# KC_Input_VAS_Schematic_v0_2.net
KiCad netlist of a schematic drawn in Altium Designer
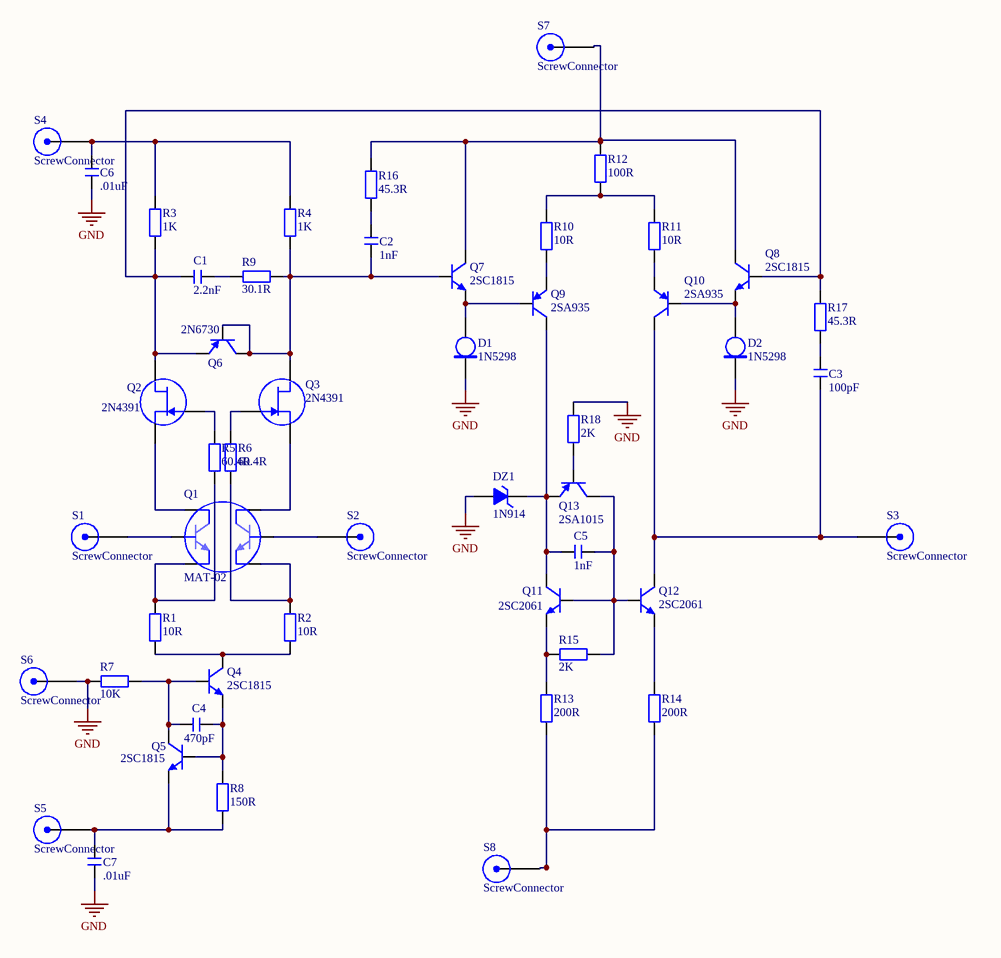
[diagram p0: KC_Input_VAS_Schematic_v0.2.SchDoc]

(export (version "E")
  (design (tool "Eeschema 10.0.6"))
  (components
    (comp (ref "C1")
      (value "2.2nF")
      (footprint "CBB 6.3*6.3*5")
      (description "CBB电容")
      (fields (field (name "版权归属") "源创客"))
      (libsource (lib "电阻-电容-电感") (part "C-CBB"))
    )
    (comp (ref "C2")
      (value "1nF")
      (footprint "CBB 6.3*6.3*5")
      (description "CBB电容")
      (fields (field (name "版权归属") "源创客"))
      (libsource (lib "电阻-电容-电感") (part "C-CBB"))
    )
    (comp (ref "C3")
      (value "100pF")
      (footprint "CBB 6.3*6.3*5")
      (description "CBB电容")
      (fields (field (name "版权归属") "源创客"))
      (libsource (lib "电阻-电容-电感") (part "C-CBB"))
    )
    (comp (ref "C4")
      (value "470pF")
      (footprint "CBB 6.3*6.3*5")
      (description "CBB电容")
      (fields (field (name "版权归属") "源创客"))
      (libsource (lib "电阻-电容-电感") (part "C-CBB"))
    )
    (comp (ref "C5")
      (value "1nF")
      (footprint "CBB 6.3*6.3*5")
      (description "CBB电容")
      (fields (field (name "版权归属") "源创客"))
      (libsource (lib "电阻-电容-电感") (part "C-CBB"))
    )
    (comp (ref "C6")
      (value ".01uF")
      (footprint "CBB 6.3*6.3*5")
      (description "CBB电容")
      (fields (field (name "版权归属") "源创客"))
      (libsource (lib "电阻-电容-电感") (part "C-CBB"))
    )
    (comp (ref "C7")
      (value ".01uF")
      (footprint "CBB 6.3*6.3*5")
      (description "CBB电容")
      (fields (field (name "版权归属") "源创客"))
      (libsource (lib "电阻-电容-电感") (part "C-CBB"))
    )
    (comp (ref "D1")
      (value "1N5298")
      (footprint "DO-41V")
      (description "Current Regulator Diodes")
      (libsource (lib "二极管-整流桥") (part "1N5xxx"))
    )
    (comp (ref "D2")
      (value "1N5298")
      (footprint "DO-41V")
      (description "Current Regulator Diodes")
      (libsource (lib "二极管-整流桥") (part "1N5xxx"))
    )
    (comp (ref "DZ1")
      (value "1N914")
      (footprint "DO-41")
      (description "3V/0.5W稳压管")
      (fields (field (name "版权归属") "源创客"))
      (libsource (lib "二极管-整流桥") (part "1N4619"))
    )
    (comp (ref "Q1")
      (value "MAT-02")
      (footprint "DIP-8")
      (description "孪生对管-NPN型 40V/20ma")
      (libsource (lib "三极管") (part "MAT-02"))
    )
    (comp (ref "Q2")
      (value "2N4391")
      (footprint "TO-18_SMALLHOLE")
      (description "N沟道JFET开关管 40V/150ma")
      (libsource (lib "场效应管") (part "2N4391"))
    )
    (comp (ref "Q3")
      (value "2N4391")
      (footprint "TO-18_SMALLHOLE")
      (description "N沟道JFET开关管 40V/150ma")
      (libsource (lib "场效应管") (part "2N4391"))
    )
    (comp (ref "Q4")
      (value "2SC1815")
      (footprint "TO92A_SmallHole")
      (description "音频放大-NPN型")
      (libsource (lib "三极管") (part "2SC1815"))
    )
    (comp (ref "Q5")
      (value "2SC1815")
      (footprint "TO92A_SmallHole")
      (description "音频放大-NPN型")
      (libsource (lib "三极管") (part "2SC1815"))
    )
    (comp (ref "Q6")
      (value "2N6730")
      (footprint "TO92A_SmallHole")
      (description "中功率放大-PNP型")
      (libsource (lib "三极管") (part "2N6728/6729/6730"))
    )
    (comp (ref "Q7")
      (value "2SC1815")
      (footprint "TO92A_SmallHole")
      (description "音频放大-NPN型")
      (libsource (lib "三极管") (part "2SC1815"))
    )
    (comp (ref "Q8")
      (value "2SC1815")
      (footprint "TO92A_SmallHole")
      (description "音频放大-NPN型")
      (libsource (lib "三极管") (part "2SC1815"))
    )
    (comp (ref "Q9")
      (value "2SA935")
      (footprint "TO92A_SmallHole")
      (description "音频功放-PNP型 50V/500ma")
      (libsource (lib "三极管") (part "2SA935"))
    )
    (comp (ref "Q10")
      (value "2SA935")
      (footprint "TO92A_SmallHole")
      (description "音频功放-PNP型 50V/500ma")
      (libsource (lib "三极管") (part "2SA935"))
    )
    (comp (ref "Q11")
      (value "2SC2061")
      (footprint "TO92A_SmallHole")
      (description "音频放大-NPN型 50V/500ma")
      (libsource (lib "三极管") (part "2SC2061"))
    )
    (comp (ref "Q12")
      (value "2SC2061")
      (footprint "TO92A_SmallHole")
      (description "音频放大-NPN型 50V/500ma")
      (libsource (lib "三极管") (part "2SC2061"))
    )
    (comp (ref "Q13")
      (value "2SA1015")
      (footprint "TO92A_SmallHole")
      (description "音频放大-PNP型")
      (libsource (lib "三极管") (part "2SA1015"))
    )
    (comp (ref "R1")
      (value "10R")
      (footprint "RS 1/4W")
      (description "直插色环电阻")
      (fields (field (name "版权归属") "源创客"))
      (libsource (lib "电阻-电容-电感") (part "R-CRR"))
    )
    (comp (ref "R2")
      (value "10R")
      (footprint "RS 1/4W")
      (description "直插色环电阻")
      (fields (field (name "版权归属") "源创客"))
      (libsource (lib "电阻-电容-电感") (part "R-CRR"))
    )
    (comp (ref "R3")
      (value "1K")
      (footprint "RS 1/4W")
      (description "直插色环电阻")
      (fields (field (name "版权归属") "源创客"))
      (libsource (lib "电阻-电容-电感") (part "R-CRR"))
    )
    (comp (ref "R4")
      (value "1K")
      (footprint "RS 1/4W")
      (description "直插色环电阻")
      (fields (field (name "版权归属") "源创客"))
      (libsource (lib "电阻-电容-电感") (part "R-CRR"))
    )
    (comp (ref "R5")
      (value "60.4R")
      (footprint "RS 1/4W")
      (description "直插色环电阻")
      (fields (field (name "版权归属") "源创客"))
      (libsource (lib "电阻-电容-电感") (part "R-CRR"))
    )
    (comp (ref "R6")
      (value "60.4R")
      (footprint "RS 1/4W")
      (description "直插色环电阻")
      (fields (field (name "版权归属") "源创客"))
      (libsource (lib "电阻-电容-电感") (part "R-CRR"))
    )
    (comp (ref "R7")
      (value "10K")
      (footprint "RS 1/4W")
      (description "直插色环电阻")
      (fields (field (name "版权归属") "源创客"))
      (libsource (lib "电阻-电容-电感") (part "R-CRR"))
    )
    (comp (ref "R8")
      (value "150R")
      (footprint "RS 1/4W")
      (description "直插色环电阻")
      (fields (field (name "版权归属") "源创客"))
      (libsource (lib "电阻-电容-电感") (part "R-CRR"))
    )
    (comp (ref "R9")
      (value "30.1R")
      (footprint "RS 1/4W")
      (description "直插色环电阻")
      (fields (field (name "版权归属") "源创客"))
      (libsource (lib "电阻-电容-电感") (part "R-CRR"))
    )
    (comp (ref "R10")
      (value "10R")
      (footprint "RS 1/4W")
      (description "直插色环电阻")
      (fields (field (name "版权归属") "源创客"))
      (libsource (lib "电阻-电容-电感") (part "R-CRR"))
    )
    (comp (ref "R11")
      (value "10R")
      (footprint "RS 1/4W")
      (description "直插色环电阻")
      (fields (field (name "版权归属") "源创客"))
      (libsource (lib "电阻-电容-电感") (part "R-CRR"))
    )
    (comp (ref "R12")
      (value "100R")
      (footprint "RS 1/4W")
      (description "直插色环电阻")
      (fields (field (name "版权归属") "源创客"))
      (libsource (lib "电阻-电容-电感") (part "R-CRR"))
    )
    (comp (ref "R13")
      (value "200R")
      (footprint "RS 1/4W")
      (description "直插色环电阻")
      (fields (field (name "版权归属") "源创客"))
      (libsource (lib "电阻-电容-电感") (part "R-CRR"))
    )
    (comp (ref "R14")
      (value "200R")
      (footprint "RS 1/4W")
      (description "直插色环电阻")
      (fields (field (name "版权归属") "源创客"))
      (libsource (lib "电阻-电容-电感") (part "R-CRR"))
    )
    (comp (ref "R15")
      (value "2K")
      (footprint "RS 1/4W")
      (description "直插色环电阻")
      (fields (field (name "版权归属") "源创客"))
      (libsource (lib "电阻-电容-电感") (part "R-CRR"))
    )
    (comp (ref "R16")
      (value "45.3R")
      (footprint "RS 1/4W")
      (description "直插色环电阻")
      (fields (field (name "版权归属") "源创客"))
      (libsource (lib "电阻-电容-电感") (part "R-CRR"))
    )
    (comp (ref "R17")
      (value "45.3R")
      (footprint "RS 1/4W")
      (description "直插色环电阻")
      (fields (field (name "版权归属") "源创客"))
      (libsource (lib "电阻-电容-电感") (part "R-CRR"))
    )
    (comp (ref "R18")
      (value "2K")
      (footprint "RS 1/4W")
      (description "直插色环电阻")
      (fields (field (name "版权归属") "源创客"))
      (libsource (lib "电阻-电容-电感") (part "R-CRR"))
    )
    (comp (ref "S1")
      (value "ScrewConnector")
      (footprint "Screw-M3")
      (description "Screw Connector")
      (libsource (lib "Connectors") (part "ScrewConnector"))
    )
    (comp (ref "S2")
      (value "ScrewConnector")
      (footprint "Screw-M3")
      (description "Screw Connector")
      (libsource (lib "Connectors") (part "ScrewConnector"))
    )
    (comp (ref "S3")
      (value "ScrewConnector")
      (footprint "Screw-M3")
      (description "Screw Connector")
      (libsource (lib "Connectors") (part "ScrewConnector"))
    )
    (comp (ref "S4")
      (value "ScrewConnector")
      (footprint "Screw-M3")
      (description "Screw Connector")
      (libsource (lib "Connectors") (part "ScrewConnector"))
    )
    (comp (ref "S5")
      (value "ScrewConnector")
      (footprint "Screw-M3")
      (description "Screw Connector")
      (libsource (lib "Connectors") (part "ScrewConnector"))
    )
    (comp (ref "S6")
      (value "ScrewConnector")
      (footprint "Screw-M3")
      (description "Screw Connector")
      (libsource (lib "Connectors") (part "ScrewConnector"))
    )
    (comp (ref "S7")
      (value "ScrewConnector")
      (footprint "Screw-M3")
      (description "Screw Connector")
      (libsource (lib "Connectors") (part "ScrewConnector"))
    )
    (comp (ref "S8")
      (value "ScrewConnector")
      (footprint "Screw-M3")
      (description "Screw Connector")
      (libsource (lib "Connectors") (part "ScrewConnector"))
    )
  )
  (nets
    (net (code "1") (name "GND") (class "Default")
      (node (ref "C6") (pin "2") (pinfunction "2_2") (pintype "passive"))
      (node (ref "C7") (pin "1") (pinfunction "1_1") (pintype "passive"))
      (node (ref "D1") (pin "1") (pinfunction "Cathode_1") (pintype "passive"))
      (node (ref "D2") (pin "1") (pinfunction "Cathode_1") (pintype "passive"))
      (node (ref "DZ1") (pin "1") (pinfunction "A_1") (pintype "passive"))
      (node (ref "R18") (pin "2") (pinfunction "2_2") (pintype "passive"))
      (node (ref "R7") (pin "1") (pinfunction "1_1") (pintype "passive"))
      (node (ref "S6") (pin "1") (pinfunction "X_1") (pintype "passive"))
    )
    (net (code "2") (name "Net-(C1-Pad2)") (class "Default")
      (node (ref "C1") (pin "2") (pinfunction "2_2") (pintype "passive"))
      (node (ref "R9") (pin "1") (pinfunction "1_1") (pintype "passive"))
    )
    (net (code "3") (name "Net-(C2-Pad1)") (class "Default")
      (node (ref "C2") (pin "1") (pinfunction "1_1") (pintype "passive"))
      (node (ref "R16") (pin "1") (pinfunction "1_1") (pintype "passive"))
    )
    (net (code "4") (name "Net-(C3-Pad2)") (class "Default")
      (node (ref "C3") (pin "2") (pinfunction "2_2") (pintype "passive"))
      (node (ref "R17") (pin "1") (pinfunction "1_1") (pintype "passive"))
    )
    (net (code "5") (name "Net-(D1-Anode)") (class "Default")
      (node (ref "D1") (pin "2") (pinfunction "Anode_2") (pintype "passive"))
      (node (ref "Q7") (pin "1") (pinfunction "E_1") (pintype "passive"))
      (node (ref "Q9") (pin "3") (pinfunction "B_3") (pintype "passive"))
    )
    (net (code "6") (name "Net-(D2-Anode)") (class "Default")
      (node (ref "D2") (pin "2") (pinfunction "Anode_2") (pintype "passive"))
      (node (ref "Q10") (pin "3") (pinfunction "B_3") (pintype "passive"))
      (node (ref "Q8") (pin "1") (pinfunction "E_1") (pintype "passive"))
    )
    (net (code "7") (name "Net-(DZ1-K)") (class "Default")
      (node (ref "C5") (pin "1") (pinfunction "1_1") (pintype "passive"))
      (node (ref "DZ1") (pin "2") (pinfunction "K_2") (pintype "passive"))
      (node (ref "Q11") (pin "2") (pinfunction "C_2") (pintype "passive"))
      (node (ref "Q13") (pin "1") (pinfunction "E_1") (pintype "passive"))
      (node (ref "Q9") (pin "2") (pinfunction "C_2") (pintype "passive"))
    )
    (net (code "8") (name "Net-(Q1-E-Pad3)") (class "Default")
      (node (ref "Q1") (pin "3") (pinfunction "E_3") (pintype "passive"))
      (node (ref "R1") (pin "2") (pinfunction "2_2") (pintype "passive"))
      (node (ref "R5") (pin "1") (pinfunction "1_1") (pintype "passive"))
    )
    (net (code "9") (name "Net-(Q1-E-Pad5)") (class "Default")
      (node (ref "Q1") (pin "5") (pinfunction "E_5") (pintype "passive"))
      (node (ref "R2") (pin "2") (pinfunction "2_2") (pintype "passive"))
      (node (ref "R6") (pin "1") (pinfunction "1_1") (pintype "passive"))
    )
    (net (code "10") (name "Net-(Q2-D)") (class "Default")
      (node (ref "C1") (pin "1") (pinfunction "1_1") (pintype "passive"))
      (node (ref "Q2") (pin "3") (pinfunction "D_3") (pintype "passive"))
      (node (ref "Q6") (pin "1") (pinfunction "E_1") (pintype "passive"))
      (node (ref "Q8") (pin "3") (pinfunction "B_3") (pintype "passive"))
      (node (ref "R17") (pin "2") (pinfunction "2_2") (pintype "passive"))
      (node (ref "R3") (pin "1") (pinfunction "1_1") (pintype "passive"))
    )
    (net (code "11") (name "Net-(Q2-G)") (class "Default")
      (node (ref "Q2") (pin "2") (pinfunction "G_2") (pintype "passive"))
      (node (ref "R5") (pin "2") (pinfunction "2_2") (pintype "passive"))
    )
    (net (code "12") (name "Net-(Q2-S)") (class "Default")
      (node (ref "Q1") (pin "1") (pinfunction "C_1") (pintype "passive"))
      (node (ref "Q2") (pin "1") (pinfunction "S_1") (pintype "passive"))
    )
    (net (code "13") (name "Net-(Q3-D)") (class "Default")
      (node (ref "C2") (pin "2") (pinfunction "2_2") (pintype "passive"))
      (node (ref "Q3") (pin "3") (pinfunction "D_3") (pintype "passive"))
      (node (ref "Q6") (pin "2") (pinfunction "C_2") (pintype "passive"))
      (node (ref "Q6") (pin "3") (pinfunction "B_3") (pintype "passive"))
      (node (ref "Q7") (pin "3") (pinfunction "B_3") (pintype "passive"))
      (node (ref "R4") (pin "1") (pinfunction "1_1") (pintype "passive"))
      (node (ref "R9") (pin "2") (pinfunction "2_2") (pintype "passive"))
    )
    (net (code "14") (name "Net-(Q3-G)") (class "Default")
      (node (ref "Q3") (pin "2") (pinfunction "G_2") (pintype "passive"))
      (node (ref "R6") (pin "2") (pinfunction "2_2") (pintype "passive"))
    )
    (net (code "15") (name "Net-(Q3-S)") (class "Default")
      (node (ref "Q1") (pin "7") (pinfunction "C_7") (pintype "passive"))
      (node (ref "Q3") (pin "1") (pinfunction "S_1") (pintype "passive"))
    )
    (net (code "16") (name "Net-(Q4-B)") (class "Default")
      (node (ref "C4") (pin "1") (pinfunction "1_1") (pintype "passive"))
      (node (ref "Q4") (pin "3") (pinfunction "B_3") (pintype "passive"))
      (node (ref "Q5") (pin "2") (pinfunction "C_2") (pintype "passive"))
      (node (ref "R7") (pin "2") (pinfunction "2_2") (pintype "passive"))
    )
    (net (code "17") (name "Net-(Q4-C)") (class "Default")
      (node (ref "Q4") (pin "2") (pinfunction "C_2") (pintype "passive"))
      (node (ref "R1") (pin "1") (pinfunction "1_1") (pintype "passive"))
      (node (ref "R2") (pin "1") (pinfunction "1_1") (pintype "passive"))
    )
    (net (code "18") (name "Net-(Q4-E)") (class "Default")
      (node (ref "C4") (pin "2") (pinfunction "2_2") (pintype "passive"))
      (node (ref "Q4") (pin "1") (pinfunction "E_1") (pintype "passive"))
      (node (ref "Q5") (pin "3") (pinfunction "B_3") (pintype "passive"))
      (node (ref "R8") (pin "1") (pinfunction "1_1") (pintype "passive"))
    )
    (net (code "19") (name "Net-(Q5-E)") (class "Default")
      (node (ref "C7") (pin "2") (pinfunction "2_2") (pintype "passive"))
      (node (ref "Q5") (pin "1") (pinfunction "E_1") (pintype "passive"))
      (node (ref "R8") (pin "2") (pinfunction "2_2") (pintype "passive"))
      (node (ref "S5") (pin "1") (pinfunction "X_1") (pintype "passive"))
    )
    (net (code "20") (name "Net-(Q7-C)") (class "Default")
      (node (ref "Q7") (pin "2") (pinfunction "C_2") (pintype "passive"))
      (node (ref "Q8") (pin "2") (pinfunction "C_2") (pintype "passive"))
      (node (ref "R12") (pin "2") (pinfunction "2_2") (pintype "passive"))
      (node (ref "R16") (pin "2") (pinfunction "2_2") (pintype "passive"))
      (node (ref "S7") (pin "1") (pinfunction "X_1") (pintype "passive"))
    )
    (net (code "21") (name "Net-(Q9-E)") (class "Default")
      (node (ref "Q9") (pin "1") (pinfunction "E_1") (pintype "passive"))
      (node (ref "R10") (pin "1") (pinfunction "1_1") (pintype "passive"))
    )
    (net (code "22") (name "Net-(Q10-C)") (class "Default")
      (node (ref "C3") (pin "1") (pinfunction "1_1") (pintype "passive"))
      (node (ref "Q10") (pin "2") (pinfunction "C_2") (pintype "passive"))
      (node (ref "Q12") (pin "2") (pinfunction "C_2") (pintype "passive"))
      (node (ref "S3") (pin "1") (pinfunction "X_1") (pintype "passive"))
    )
    (net (code "23") (name "Net-(Q10-E)") (class "Default")
      (node (ref "Q10") (pin "1") (pinfunction "E_1") (pintype "passive"))
      (node (ref "R11") (pin "1") (pinfunction "1_1") (pintype "passive"))
    )
    (net (code "24") (name "Net-(Q11-B)") (class "Default")
      (node (ref "C5") (pin "2") (pinfunction "2_2") (pintype "passive"))
      (node (ref "Q11") (pin "3") (pinfunction "B_3") (pintype "passive"))
      (node (ref "Q12") (pin "3") (pinfunction "B_3") (pintype "passive"))
      (node (ref "Q13") (pin "2") (pinfunction "C_2") (pintype "passive"))
      (node (ref "R15") (pin "1") (pinfunction "1_1") (pintype "passive"))
    )
    (net (code "25") (name "Net-(Q11-E)") (class "Default")
      (node (ref "Q11") (pin "1") (pinfunction "E_1") (pintype "passive"))
      (node (ref "R13") (pin "2") (pinfunction "2_2") (pintype "passive"))
      (node (ref "R15") (pin "2") (pinfunction "2_2") (pintype "passive"))
    )
    (net (code "26") (name "Net-(Q12-E)") (class "Default")
      (node (ref "Q12") (pin "1") (pinfunction "E_1") (pintype "passive"))
      (node (ref "R14") (pin "2") (pinfunction "2_2") (pintype "passive"))
    )
    (net (code "27") (name "Net-(Q13-B)") (class "Default")
      (node (ref "Q13") (pin "3") (pinfunction "B_3") (pintype "passive"))
      (node (ref "R18") (pin "1") (pinfunction "1_1") (pintype "passive"))
    )
    (net (code "28") (name "Net-(R10-Pad2)") (class "Default")
      (node (ref "R10") (pin "2") (pinfunction "2_2") (pintype "passive"))
      (node (ref "R11") (pin "2") (pinfunction "2_2") (pintype "passive"))
      (node (ref "R12") (pin "1") (pinfunction "1_1") (pintype "passive"))
    )
    (net (code "29") (name "Net-(S1-X)") (class "Default")
      (node (ref "Q1") (pin "2") (pinfunction "B_2") (pintype "passive"))
      (node (ref "S1") (pin "1") (pinfunction "X_1") (pintype "passive"))
    )
    (net (code "30") (name "Net-(S2-X)") (class "Default")
      (node (ref "Q1") (pin "6") (pinfunction "B_6") (pintype "passive"))
      (node (ref "S2") (pin "1") (pinfunction "X_1") (pintype "passive"))
    )
    (net (code "31") (name "Net-(S4-X)") (class "Default")
      (node (ref "C6") (pin "1") (pinfunction "1_1") (pintype "passive"))
      (node (ref "R3") (pin "2") (pinfunction "2_2") (pintype "passive"))
      (node (ref "R4") (pin "2") (pinfunction "2_2") (pintype "passive"))
      (node (ref "S4") (pin "1") (pinfunction "X_1") (pintype "passive"))
    )
    (net (code "32") (name "Net-(S8-X)") (class "Default")
      (node (ref "R13") (pin "1") (pinfunction "1_1") (pintype "passive"))
      (node (ref "R14") (pin "1") (pinfunction "1_1") (pintype "passive"))
      (node (ref "S8") (pin "1") (pinfunction "X_1") (pintype "passive"))
    )
  )
)
